# Power.net
KiCad netlist of a schematic drawn in Altium Designer
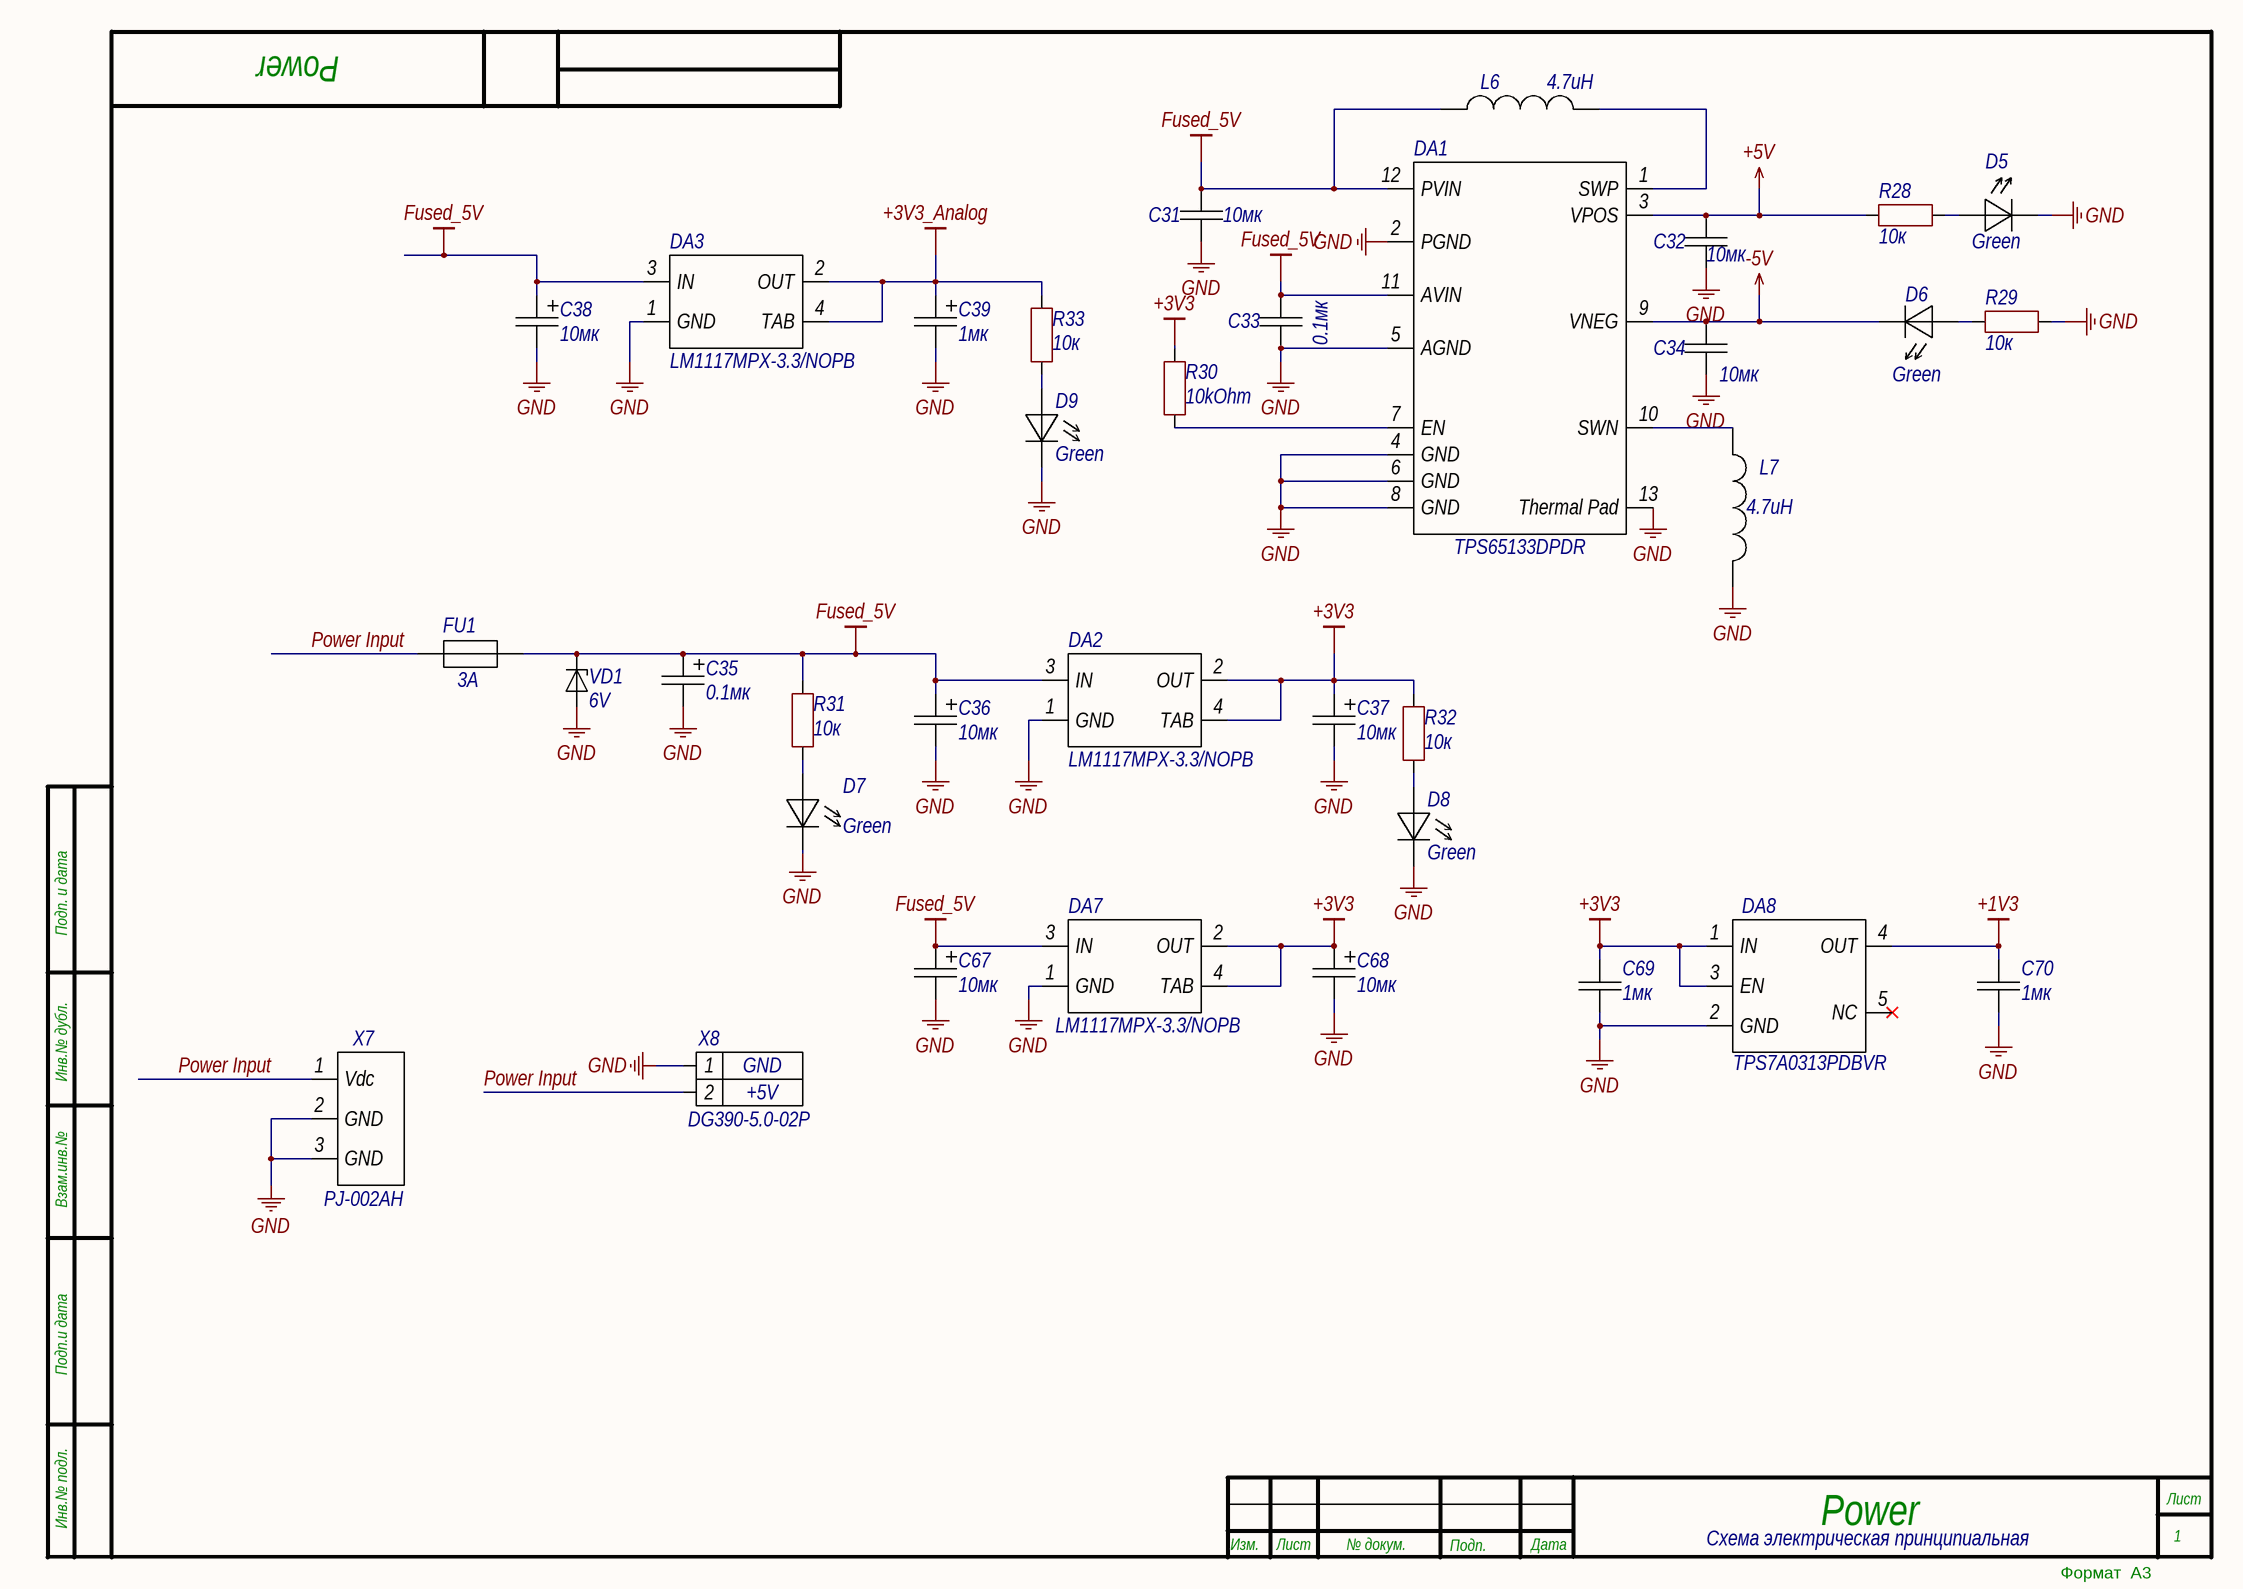
[diagram p0: Power.SchDoc]

(export (version "E")
  (design (tool "Eeschema 10.0.6"))
  (components
    (comp (ref "C31")
      (value "10мк")
      (footprint "CAPC3216N")
      (fields (field (name "PART NUMBER") "CAPC") (field (name "Comment") "10мк *"))
      (libsource (lib "Library") (part "CAPC"))
    )
    (comp (ref "C32")
      (value "10мк")
      (footprint "CAPC3216N")
      (fields (field (name "PART NUMBER") "CAPC") (field (name "Comment") "10мк *"))
      (libsource (lib "Library") (part "CAPC"))
    )
    (comp (ref "C33")
      (value "0.1мк")
      (footprint "CAPC3216N")
      (fields (field (name "PART NUMBER") "CAPC") (field (name "Comment") "0.1мк *"))
      (libsource (lib "Library") (part "CAPC"))
    )
    (comp (ref "C34")
      (value "10мк")
      (footprint "CAPC3216N")
      (fields (field (name "PART NUMBER") "CAPC") (field (name "Comment") "10мк *"))
      (libsource (lib "Library") (part "CAPC"))
    )
    (comp (ref "C35")
      (value "0.1мк")
      (footprint "TYPEB")
      (fields
        (field (name "MANUFACTURER") "KEMET")
        (field (name "MPN") "T491B107M010AT")
        (field (name "TOLERANCE") "20%")
      )
      (libsource (lib "Library") (part "Cap TANTAL"))
    )
    (comp (ref "C36")
      (value "10мк")
      (footprint "TYPEA")
      (fields
        (field (name "MANUFACTURER") "AVX")
        (field (name "MPN") "TAJA106K016RNJ")
        (field (name "TOLERANCE") "10%")
      )
      (libsource (lib "Library") (part "Cap TANTAL"))
    )
    (comp (ref "C37")
      (value "10мк")
      (footprint "TYPEA")
      (fields
        (field (name "MANUFACTURER") "AVX")
        (field (name "MPN") "TAJA106K016RNJ")
        (field (name "TOLERANCE") "10%")
      )
      (libsource (lib "Library") (part "Cap TANTAL"))
    )
    (comp (ref "C38")
      (value "10мк")
      (footprint "TYPEA")
      (fields
        (field (name "MANUFACTURER") "AVX")
        (field (name "MPN") "TAJA106K016RNJ")
        (field (name "TOLERANCE") "10%")
      )
      (libsource (lib "Library") (part "Cap TANTAL"))
    )
    (comp (ref "C39")
      (value "1мк")
      (footprint "TYPEA")
      (fields
        (field (name "MANUFACTURER") "AVX")
        (field (name "MPN") "TAJA106K016RNJ")
        (field (name "TOLERANCE") "10%")
      )
      (libsource (lib "Library") (part "Cap TANTAL"))
    )
    (comp (ref "C67")
      (value "10мк")
      (footprint "TYPEA")
      (fields (field (name "PART NUMBER") "Cap TANTAL") (field (name "Comment") "10мк "))
      (libsource (lib "Library") (part "Cap TANTAL"))
    )
    (comp (ref "C68")
      (value "10мк")
      (footprint "TYPEA")
      (fields (field (name "PART NUMBER") "Cap TANTAL") (field (name "Comment") "10мк "))
      (libsource (lib "Library") (part "Cap TANTAL"))
    )
    (comp (ref "C69")
      (value "1мк")
      (footprint "CAP0402")
      (fields (field (name "PART NUMBER") "CAP0402") (field (name "Comment") "1мк *"))
      (libsource (lib "Library") (part "CAPC"))
    )
    (comp (ref "C70")
      (value "1мк")
      (footprint "CAP0402")
      (fields (field (name "PART NUMBER") "CAP0402") (field (name "Comment") "1мк *"))
      (libsource (lib "Library") (part "CAPC"))
    )
    (comp (ref "D5")
      (value "Green")
      (footprint "LED603")
      (fields (field (name "PART NUMBER") "LEDC"))
      (libsource (lib "Library") (part "LEDC"))
    )
    (comp (ref "D6")
      (value "Green")
      (footprint "LED603")
      (fields (field (name "PART NUMBER") "LEDC"))
      (libsource (lib "Library") (part "LEDC"))
    )
    (comp (ref "D7")
      (value "Green")
      (footprint "LED603")
      (fields
        (field (name "MANUFACTURER") "Everlight Elec")
        (field (name "MPN") "19-217/GHC-YR1S2/3T")
        (field (name "POWER") "110mW")
      )
      (libsource (lib "Library") (part "LEDC"))
    )
    (comp (ref "D8")
      (value "Green")
      (footprint "LED603")
      (fields (field (name "PART NUMBER") "LEDC"))
      (libsource (lib "Library") (part "LEDC"))
    )
    (comp (ref "D9")
      (value "Green")
      (footprint "LED603")
      (fields (field (name "PART NUMBER") "LEDC"))
      (libsource (lib "Library") (part "LEDC"))
    )
    (comp (ref "DA1")
      (value "TPS65133DPDR")
      (footprint "FP-DPD0012A-IPC_A")
      (description "Dual-Output Power Supply")
      (fields (field (name "MANUFACTURER") "TI"))
      (libsource (lib "Library") (part "TPS65133DPDR"))
    )
    (comp (ref "DA2")
      (value "LDO 5V to 3V3")
      (footprint "SOT-223")
      (fields
        (field (name "MANUFACTURER") "Texas Instruments")
        (field (name "MPN") "LM1117MPX-3.3/NOPB")
        (field (name "VOLTAGE") "15V")
        (field (name "PART NUMBER") "LM1117MPX-3.3/NOPB")
      )
      (libsource (lib "Library") (part "LM1117"))
    )
    (comp (ref "DA3")
      (value "LDO 5V to 3V3")
      (footprint "SOT-223")
      (fields
        (field (name "MANUFACTURER") "Texas Instruments")
        (field (name "MPN") "LM1117MPX-3.3/NOPB")
        (field (name "VOLTAGE") "15V")
        (field (name "PART NUMBER") "LM1117MPX-3.3/NOPB")
      )
      (libsource (lib "Library") (part "LM1117"))
    )
    (comp (ref "DA7")
      (value "LM1117MPX-3.3/NOPB")
      (footprint "SOT-223")
      (fields
        (field (name "MANUFACTURER") "Texas Instruments")
        (field (name "VOLTAGE") "3.3V")
        (field (name "PART NUMBER") "LM1117MPX-3.3/NOPB")
      )
      (libsource (lib "Library") (part "LM1117"))
    )
    (comp (ref "DA8")
      (value "TPS7A0313PDBVR")
      (footprint "SOT-23-5")
      (fields (field (name "MANUFACTURER") "TI") (field (name "MPN") "TPS7A0313PDBVR"))
      (libsource (lib "Library") (part "TPS7A0313PDBVR"))
    )
    (comp (ref "FU1")
      (value "3A")
      (footprint "FP-0154-MFG")
      (fields
        (field (name "PART NUMBER") "0154003.DR")
        (field (name "MANUFACTURER") "Littelfuse")
        (field (name "VOLTAGE") "125 V")
      )
      (libsource (lib "Library") (part "Fuse"))
    )
    (comp (ref "L6")
      (value "4.7uH")
      (footprint "ind_SRN8040")
      (fields (field (name "MANUFACTURER") "Bourns") (field (name "MPN") "SRN8040-4R7Y"))
      (libsource (lib "Library") (part "Inductor"))
    )
    (comp (ref "L7")
      (value "4.7uH")
      (footprint "ind_SRN8040")
      (fields (field (name "MANUFACTURER") "Bourns") (field (name "MPN") "SRN8040-4R7Y"))
      (libsource (lib "Library") (part "Inductor"))
    )
    (comp (ref "R28")
      (value "10к")
      (footprint "RESC0603N")
      (fields (field (name "PART NUMBER") "RES") (field (name "Comment") "10к "))
      (libsource (lib "Library") (part "RES"))
    )
    (comp (ref "R29")
      (value "10к")
      (footprint "RESC0603N")
      (fields (field (name "PART NUMBER") "RES") (field (name "Comment") "10к "))
      (libsource (lib "Library") (part "RES"))
    )
    (comp (ref "R30")
      (value "10kOhm")
      (footprint "RESC0603N")
      (fields
        (field (name "MANUFACTURER") "UNI-ROYAL(Uniroyal Elec)")
        (field (name "MPN") "0603WAF1002T5E")
        (field (name "POWER") "0.1W")
      )
      (libsource (lib "") (part "RES_1"))
    )
    (comp (ref "R31")
      (value "10к")
      (footprint "RESC0603N")
      (fields
        (field (name "MANUFACTURER") "UNI-ROYAL(Uniroyal Elec)")
        (field (name "MPN") "0603WAF1002T5E")
        (field (name "POWER") "0.1W")
      )
      (libsource (lib "") (part "RES_1"))
    )
    (comp (ref "R32")
      (value "10к")
      (footprint "RESC0603N")
      (fields (field (name "PART NUMBER") "RES") (field (name "Comment") "10к "))
      (libsource (lib "") (part "RES_1"))
    )
    (comp (ref "R33")
      (value "10к")
      (footprint "RESC0603N")
      (fields (field (name "PART NUMBER") "RES") (field (name "Comment") "10к "))
      (libsource (lib "") (part "RES_1"))
    )
    (comp (ref "VD1")
      (value "6V")
      (footprint "DO-214AA")
      (fields
        (field (name "PART NUMBER") "SMBJ6.0A")
        (field (name "MANUFACTURER") "RUILON(Shenzhen Ruilongyuan Elec)")
        (field (name "POWER") "5W")
      )
      (libsource (lib "Library") (part "diode_zener"))
    )
    (comp (ref "X7")
      (value "PJ-002AH")
      (footprint "PJ-002AH")
      (fields (field (name "MANUFACTURER") "CUI") (field (name "PART NUMBER") "CUI_PJ-002AH"))
      (libsource (lib "Library") (part "CONN_DIP_2MM_3PIN"))
    )
    (comp (ref "X8")
      (value "DG390-5.0-02P")
      (footprint "DG390-5.0-02P")
      (fields
        (field (name "WIRE2") "+5V")
        (field (name "WIRE1") "GND")
        (field (name "MANUFACTURER") "DEGSON")
      )
      (libsource (lib "Library") (part "Connector_2pin"))
    )
  )
  (nets
    (net (code "1") (name "+1V3") (class "Default")
      (node (ref "C70") (pin "2") (pinfunction "2_2") (pintype "passive"))
      (node (ref "DA8") (pin "4") (pinfunction "OUT_4") (pintype "passive"))
    )
    (net (code "2") (name "+3V3") (class "Default")
      (node (ref "C37") (pin "1") (pintype "passive"))
      (node (ref "C68") (pin "1") (pintype "passive"))
      (node (ref "C69") (pin "2") (pinfunction "2_2") (pintype "passive"))
      (node (ref "DA2") (pin "2") (pinfunction "OUT_2") (pintype "passive"))
      (node (ref "DA2") (pin "4") (pinfunction "TAB_4") (pintype "passive"))
      (node (ref "DA7") (pin "2") (pinfunction "OUT_2") (pintype "passive"))
      (node (ref "DA7") (pin "4") (pinfunction "TAB_4") (pintype "passive"))
      (node (ref "DA8") (pin "1") (pinfunction "IN_1") (pintype "passive"))
      (node (ref "DA8") (pin "3") (pinfunction "EN_3") (pintype "passive"))
      (node (ref "R30") (pin "2") (pinfunction "2_2") (pintype "passive"))
      (node (ref "R32") (pin "2") (pinfunction "2_2") (pintype "passive"))
    )
    (net (code "3") (name "+3V3_Analog") (class "Default")
      (node (ref "C39") (pin "1") (pintype "passive"))
      (node (ref "DA3") (pin "2") (pinfunction "OUT_2") (pintype "passive"))
      (node (ref "DA3") (pin "4") (pinfunction "TAB_4") (pintype "passive"))
      (node (ref "R33") (pin "2") (pinfunction "2_2") (pintype "passive"))
    )
    (net (code "4") (name "+5V") (class "Default")
      (node (ref "C32") (pin "2") (pinfunction "2_2") (pintype "passive"))
      (node (ref "DA1") (pin "3") (pinfunction "VPOS_3") (pintype "passive"))
      (node (ref "R28") (pin "1") (pinfunction "1_1") (pintype "passive"))
    )
    (net (code "5") (name "-5V") (class "Default")
      (node (ref "C34") (pin "2") (pinfunction "2_2") (pintype "passive"))
      (node (ref "D6") (pin "1") (pinfunction "A_1") (pintype "passive"))
      (node (ref "DA1") (pin "9") (pinfunction "VNEG_9") (pintype "passive"))
    )
    (net (code "6") (name "/Power Input") (class "Default")
      (node (ref "FU1") (pin "1") (pinfunction "1_1") (pintype "passive"))
      (node (ref "X7") (pin "1") (pinfunction "Vdc_1") (pintype "passive"))
      (node (ref "X8") (pin "2") (pinfunction "2_2") (pintype "passive"))
    )
    (net (code "7") (name "Fused_5V") (class "Default")
      (node (ref "C31") (pin "2") (pinfunction "2_2") (pintype "passive"))
      (node (ref "C33") (pin "2") (pinfunction "2_2") (pintype "passive"))
      (node (ref "C35") (pin "1") (pintype "passive"))
      (node (ref "C36") (pin "1") (pintype "passive"))
      (node (ref "C38") (pin "1") (pintype "passive"))
      (node (ref "C67") (pin "1") (pintype "passive"))
      (node (ref "DA1") (pin "11") (pinfunction "AVIN_11") (pintype "passive"))
      (node (ref "DA1") (pin "12") (pinfunction "PVIN_12") (pintype "passive"))
      (node (ref "DA2") (pin "3") (pinfunction "IN_3") (pintype "passive"))
      (node (ref "DA3") (pin "3") (pinfunction "IN_3") (pintype "passive"))
      (node (ref "DA7") (pin "3") (pinfunction "IN_3") (pintype "passive"))
      (node (ref "FU1") (pin "2") (pinfunction "2_2") (pintype "passive"))
      (node (ref "L6") (pin "1") (pinfunction "1_1") (pintype "passive"))
      (node (ref "R31") (pin "2") (pinfunction "2_2") (pintype "passive"))
      (node (ref "VD1") (pin "1") (pinfunction "1_1") (pintype "passive"))
    )
    (net (code "8") (name "GND") (class "Default")
      (node (ref "C31") (pin "1") (pinfunction "1_1") (pintype "passive"))
      (node (ref "C32") (pin "1") (pinfunction "1_1") (pintype "passive"))
      (node (ref "C33") (pin "1") (pinfunction "1_1") (pintype "passive"))
      (node (ref "C34") (pin "1") (pinfunction "1_1") (pintype "passive"))
      (node (ref "C35") (pin "2") (pintype "passive"))
      (node (ref "C36") (pin "2") (pintype "passive"))
      (node (ref "C37") (pin "2") (pintype "passive"))
      (node (ref "C38") (pin "2") (pintype "passive"))
      (node (ref "C39") (pin "2") (pintype "passive"))
      (node (ref "C67") (pin "2") (pintype "passive"))
      (node (ref "C68") (pin "2") (pintype "passive"))
      (node (ref "C69") (pin "1") (pinfunction "1_1") (pintype "passive"))
      (node (ref "C70") (pin "1") (pinfunction "1_1") (pintype "passive"))
      (node (ref "D5") (pin "1") (pinfunction "A_1") (pintype "passive"))
      (node (ref "D7") (pin "1") (pinfunction "A_1") (pintype "passive"))
      (node (ref "D8") (pin "1") (pinfunction "A_1") (pintype "passive"))
      (node (ref "D9") (pin "1") (pinfunction "A_1") (pintype "passive"))
      (node (ref "DA1") (pin "13") (pinfunction "Thermal_Pad_13") (pintype "passive"))
      (node (ref "DA1") (pin "2") (pinfunction "PGND_2") (pintype "passive"))
      (node (ref "DA1") (pin "4") (pinfunction "GND_4") (pintype "passive"))
      (node (ref "DA1") (pin "5") (pinfunction "AGND_5") (pintype "passive"))
      (node (ref "DA1") (pin "6") (pinfunction "GND_6") (pintype "passive"))
      (node (ref "DA1") (pin "8") (pinfunction "GND_8") (pintype "passive"))
      (node (ref "DA2") (pin "1") (pinfunction "GND_1") (pintype "passive"))
      (node (ref "DA3") (pin "1") (pinfunction "GND_1") (pintype "passive"))
      (node (ref "DA7") (pin "1") (pinfunction "GND_1") (pintype "passive"))
      (node (ref "DA8") (pin "2") (pinfunction "GND_2") (pintype "passive"))
      (node (ref "L7") (pin "2") (pinfunction "2_2") (pintype "passive"))
      (node (ref "R29") (pin "2") (pinfunction "2_2") (pintype "passive"))
      (node (ref "VD1") (pin "2") (pinfunction "2_2") (pintype "passive"))
      (node (ref "X7") (pin "2") (pinfunction "GND_2") (pintype "passive"))
      (node (ref "X7") (pin "3") (pinfunction "GND_3") (pintype "passive"))
      (node (ref "X8") (pin "1") (pinfunction "1_1") (pintype "passive"))
    )
    (net (code "9") (name "Net-(D5-K)") (class "Default")
      (node (ref "D5") (pin "2") (pinfunction "K_2") (pintype "passive"))
      (node (ref "R28") (pin "2") (pinfunction "2_2") (pintype "passive"))
    )
    (net (code "10") (name "Net-(D6-K)") (class "Default")
      (node (ref "D6") (pin "2") (pinfunction "K_2") (pintype "passive"))
      (node (ref "R29") (pin "1") (pinfunction "1_1") (pintype "passive"))
    )
    (net (code "11") (name "Net-(D7-K)") (class "Default")
      (node (ref "D7") (pin "2") (pinfunction "K_2") (pintype "passive"))
      (node (ref "R31") (pin "1") (pinfunction "1_1") (pintype "passive"))
    )
    (net (code "12") (name "Net-(D8-K)") (class "Default")
      (node (ref "D8") (pin "2") (pinfunction "K_2") (pintype "passive"))
      (node (ref "R32") (pin "1") (pinfunction "1_1") (pintype "passive"))
    )
    (net (code "13") (name "Net-(D9-K)") (class "Default")
      (node (ref "D9") (pin "2") (pinfunction "K_2") (pintype "passive"))
      (node (ref "R33") (pin "1") (pinfunction "1_1") (pintype "passive"))
    )
    (net (code "14") (name "Net-(DA1-EN)") (class "Default")
      (node (ref "DA1") (pin "7") (pinfunction "EN_7") (pintype "passive"))
      (node (ref "R30") (pin "1") (pinfunction "1_1") (pintype "passive"))
    )
    (net (code "15") (name "Net-(DA1-SWN)") (class "Default")
      (node (ref "DA1") (pin "10") (pinfunction "SWN_10") (pintype "passive"))
      (node (ref "L7") (pin "1") (pinfunction "1_1") (pintype "passive"))
    )
    (net (code "16") (name "Net-(DA1-SWP)") (class "Default")
      (node (ref "DA1") (pin "1") (pinfunction "SWP_1") (pintype "passive"))
      (node (ref "L6") (pin "2") (pinfunction "2_2") (pintype "passive"))
    )
    (net (code "17") (name "unconnected-(DA8-NC-Pad5)") (class "Default")
      (node (ref "DA8") (pin "5") (pinfunction "NC_5") (pintype "passive+no_connect"))
    )
  )
)
